# SynchronousRectifier.net
KiCad netlist of a schematic drawn in Altium Designer
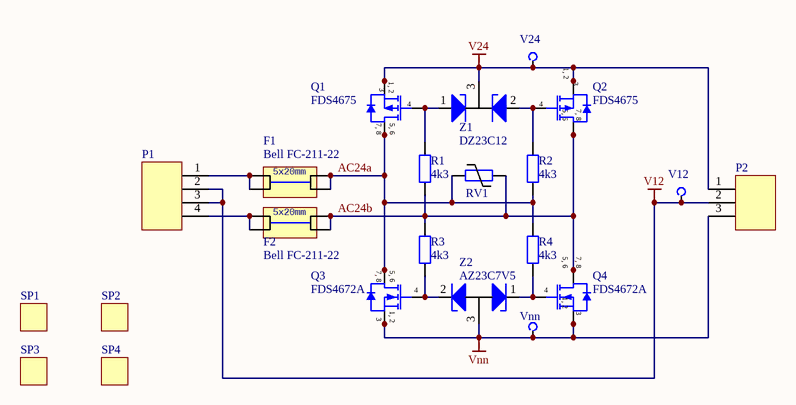
[diagram p0: SynchronousRectifier.SchDoc]

(export (version "E")
  (design (tool "Eeschema 10.0.6"))
  (components
    (comp (ref "F1")
      (value "Bell FC-211-22")
      (footprint "FUSE_CLIP_5x20")
      (description "5x20mm fuse clip PCB Mount")
      (libsource (lib "MySchLib") (part "FUSE_CLIP_5x20"))
    )
    (comp (ref "F2")
      (value "Bell FC-211-22")
      (footprint "FUSE_CLIP_5x20")
      (description "5x20mm fuse clip PCB Mount")
      (libsource (lib "MySchLib") (part "FUSE_CLIP_5x20"))
    )
    (comp (ref "P1")
      (value "Terminal4_5.08mm")
      (footprint "MOLEX-39544-3004")
      (description "MULTICOMP MC24368 TERMINAL BLOCK EUROSTYLE, 4 POSITION, 26-12AWG, 5.08mm")
      (libsource (lib "MyLibrary") (part "Terminal4_5.08mm"))
    )
    (comp (ref "P2")
      (value "Terminal3_5.08mm")
      (footprint "MOLEX-39544-3003")
      (description "MULTICOMP MC24367 TERMINAL BLOCK EUROSTYLE, 3 POSITION, 26-12AWG, 5.08mm")
      (libsource (lib "MyLibrary") (part "Terminal3_5.08mm"))
    )
    (comp (ref "Q1")
      (value "FDS4675")
      (footprint "SO-8_M")
      (fields (field (name "MANUFACTURER") "Fairchild Semiconductor"))
      (libsource (lib "MySchLib") (part "FDS4675"))
    )
    (comp (ref "Q2")
      (value "FDS4675")
      (footprint "SO-8_M")
      (fields (field (name "MANUFACTURER") "Fairchild Semiconductor"))
      (libsource (lib "MySchLib") (part "FDS4675"))
    )
    (comp (ref "Q3")
      (value "FDS4672A")
      (footprint "SO-8_M")
      (description "N-Channel Power MOSFET, 11 A, 40 V. RDS(ON)  = .013 ohm @ VGS = 4.5 V")
      (fields (field (name "MANUFACTURER") "Fairchild Semiconductor"))
      (libsource (lib "MySchLib") (part "FDS4672A"))
    )
    (comp (ref "Q4")
      (value "FDS4672A")
      (footprint "SO-8_M")
      (description "N-Channel Power MOSFET, 11 A, 40 V. RDS(ON)  = .013 ohm @ VGS = 4.5 V")
      (fields (field (name "MANUFACTURER") "Fairchild Semiconductor"))
      (libsource (lib "MySchLib") (part "FDS4672A"))
    )
    (comp (ref "R1")
      (value "4k3")
      (footprint "CR1608-0603_N")
      (description "Resistor SMT 0603")
      (fields
        (field (name "MANUFACTURER") "Generic Components")
        (field (name "PUBLISHER") "Altium Hobart Technology Centre")
      )
      (libsource (lib "MySchLib") (part "Res_CR0603"))
    )
    (comp (ref "R2")
      (value "4k3")
      (footprint "CR1608-0603_N")
      (description "Resistor SMT 0603")
      (fields
        (field (name "MANUFACTURER") "Generic Components")
        (field (name "PUBLISHER") "Altium Hobart Technology Centre")
      )
      (libsource (lib "MySchLib") (part "Res_CR0603"))
    )
    (comp (ref "R3")
      (value "4k3")
      (footprint "CR1608-0603_N")
      (description "Resistor SMT 0603")
      (fields
        (field (name "MANUFACTURER") "Generic Components")
        (field (name "PUBLISHER") "Altium Hobart Technology Centre")
      )
      (libsource (lib "MySchLib") (part "Res_CR0603"))
    )
    (comp (ref "R4")
      (value "4k3")
      (footprint "CR1608-0603_N")
      (description "Resistor SMT 0603")
      (fields
        (field (name "MANUFACTURER") "Generic Components")
        (field (name "PUBLISHER") "Altium Hobart Technology Centre")
      )
      (libsource (lib "MySchLib") (part "Res_CR0603"))
    )
    (comp (ref "RV1")
      (value "V33MLA1206NHAUTO")
      (footprint "VR3216-1206")
      (fields
        (field (name "MANUFACTURER") "Generic Components")
        (field (name "PUBLISHER") "Altium Hobart Technology Centre")
      )
      (libsource (lib "MySchLib") (part "V33MLA1206NHAUTO"))
    )
    (comp (ref "SP1")
      (value "Spacer-3mm-tapped x 10mm")
      (footprint "Spacer-3mm tapped x 10 mm")
      (description "6MM Spacer")
      (libsource (lib "MyLibrary") (part "Spacer-3mm-tapped x 10mm"))
    )
    (comp (ref "SP2")
      (value "Spacer-3mm-tapped x 10mm")
      (footprint "Spacer-3mm tapped x 10 mm")
      (description "6MM Spacer")
      (libsource (lib "MyLibrary") (part "Spacer-3mm-tapped x 10mm"))
    )
    (comp (ref "SP3")
      (value "Spacer-3mm-tapped x 10mm")
      (footprint "Spacer-3mm tapped x 10 mm")
      (description "6MM Spacer")
      (libsource (lib "MyLibrary") (part "Spacer-3mm-tapped x 10mm"))
    )
    (comp (ref "SP4")
      (value "Spacer-3mm-tapped x 10mm")
      (footprint "Spacer-3mm tapped x 10 mm")
      (description "6MM Spacer")
      (libsource (lib "MyLibrary") (part "Spacer-3mm-tapped x 10mm"))
    )
    (comp (ref "V12")
      (value "Power 12V FWR")
      (footprint "PCBPIN - 0.7mm")
      (description "Test Point")
      (libsource (lib "MySchLib") (part "TP"))
    )
    (comp (ref "V24")
      (value "Power 24V FWR")
      (footprint "PCBPIN - 0.7mm")
      (description "Test Point")
      (libsource (lib "MySchLib") (part "TP"))
    )
    (comp (ref "Vnn")
      (value "Power Ground")
      (footprint "PCBPIN - 0.7mm")
      (description "Test Point")
      (libsource (lib "MySchLib") (part "TP"))
    )
    (comp (ref "Z1")
      (value "DZ23C12")
      (footprint "SOT23_M")
      (description "Dual silicon planar Zener diodes")
      (libsource (lib "MySchLib") (part "DZ23Cxx"))
    )
    (comp (ref "Z2")
      (value "AZ23C7V5")
      (footprint "SOT23_M")
      (description "Dual silicon planar Zener diodes")
      (libsource (lib "MySchLib") (part "AZ23Cxx"))
    )
  )
  (nets
    (net (code "1") (name "/AC24a") (class "Default")
      (node (ref "F1") (pin "2") (pinfunction "2_2") (pintype "power_in"))
      (node (ref "F1") (pin "2a") (pinfunction "2a_2a") (pintype "power_in"))
      (node (ref "Q1") (pin "5") (pinfunction "D_5") (pintype "passive"))
      (node (ref "Q1") (pin "6") (pinfunction "D_6") (pintype "passive"))
      (node (ref "Q1") (pin "7") (pinfunction "D_7") (pintype "passive"))
      (node (ref "Q1") (pin "8") (pinfunction "D_8") (pintype "passive"))
      (node (ref "Q3") (pin "5") (pinfunction "D_5") (pintype "passive"))
      (node (ref "Q3") (pin "6") (pinfunction "D_6") (pintype "passive"))
      (node (ref "Q3") (pin "7") (pinfunction "D_7") (pintype "passive"))
      (node (ref "Q3") (pin "8") (pinfunction "D_8") (pintype "passive"))
      (node (ref "R2") (pin "1") (pinfunction "1_1") (pintype "passive"))
      (node (ref "R4") (pin "2") (pinfunction "2_2") (pintype "passive"))
      (node (ref "RV1") (pin "2") (pinfunction "2_2") (pintype "passive"))
    )
    (net (code "2") (name "/AC24b") (class "Default")
      (node (ref "F2") (pin "2") (pinfunction "2_2") (pintype "power_in"))
      (node (ref "F2") (pin "2a") (pinfunction "2a_2a") (pintype "power_in"))
      (node (ref "Q2") (pin "5") (pinfunction "D_5") (pintype "passive"))
      (node (ref "Q2") (pin "6") (pinfunction "D_6") (pintype "passive"))
      (node (ref "Q2") (pin "7") (pinfunction "D_7") (pintype "passive"))
      (node (ref "Q2") (pin "8") (pinfunction "D_8") (pintype "passive"))
      (node (ref "Q4") (pin "5") (pinfunction "D_5") (pintype "passive"))
      (node (ref "Q4") (pin "6") (pinfunction "D_6") (pintype "passive"))
      (node (ref "Q4") (pin "7") (pinfunction "D_7") (pintype "passive"))
      (node (ref "Q4") (pin "8") (pinfunction "D_8") (pintype "passive"))
      (node (ref "R1") (pin "1") (pinfunction "1_1") (pintype "passive"))
      (node (ref "R3") (pin "2") (pinfunction "2_2") (pintype "passive"))
      (node (ref "RV1") (pin "1") (pinfunction "1_1") (pintype "passive"))
    )
    (net (code "3") (name "Net-(F1-Pad1)") (class "Default")
      (node (ref "F1") (pin "1") (pintype "power_in"))
      (node (ref "F1") (pin "1a") (pinfunction "1a_1a") (pintype "power_in"))
      (node (ref "P1") (pin "1") (pinfunction "1_1") (pintype "passive"))
    )
    (net (code "4") (name "Net-(F2-Pad1)") (class "Default")
      (node (ref "F2") (pin "1") (pintype "power_in"))
      (node (ref "F2") (pin "1a") (pinfunction "1a_1a") (pintype "power_in"))
      (node (ref "P1") (pin "4") (pinfunction "4_4") (pintype "passive"))
    )
    (net (code "5") (name "Net-(Q1-G)") (class "Default")
      (node (ref "Q1") (pin "4") (pinfunction "G_4") (pintype "passive"))
      (node (ref "R1") (pin "2") (pinfunction "2_2") (pintype "passive"))
      (node (ref "Z1") (pin "1") (pinfunction "A1_1") (pintype "passive"))
    )
    (net (code "6") (name "Net-(Q2-G)") (class "Default")
      (node (ref "Q2") (pin "4") (pinfunction "G_4") (pintype "passive"))
      (node (ref "R2") (pin "2") (pinfunction "2_2") (pintype "passive"))
      (node (ref "Z1") (pin "2") (pinfunction "A2_2") (pintype "passive"))
    )
    (net (code "7") (name "Net-(Q3-G)") (class "Default")
      (node (ref "Q3") (pin "4") (pinfunction "G_4") (pintype "passive"))
      (node (ref "R3") (pin "1") (pinfunction "1_1") (pintype "passive"))
      (node (ref "Z2") (pin "2") (pinfunction "A2_2") (pintype "passive"))
    )
    (net (code "8") (name "Net-(Q4-G)") (class "Default")
      (node (ref "Q4") (pin "4") (pinfunction "G_4") (pintype "passive"))
      (node (ref "R4") (pin "1") (pinfunction "1_1") (pintype "passive"))
      (node (ref "Z2") (pin "1") (pinfunction "A1_1") (pintype "passive"))
    )
    (net (code "9") (name "V12") (class "Default")
      (node (ref "P1") (pin "2") (pinfunction "2_2") (pintype "passive"))
      (node (ref "P1") (pin "3") (pinfunction "3_3") (pintype "passive"))
      (node (ref "P2") (pin "2") (pinfunction "2_2") (pintype "passive"))
      (node (ref "V12") (pin "1") (pinfunction "TP_1") (pintype "passive"))
    )
    (net (code "10") (name "V24") (class "Default")
      (node (ref "P2") (pin "1") (pinfunction "1_1") (pintype "passive"))
      (node (ref "Q1") (pin "1") (pinfunction "S_1") (pintype "passive"))
      (node (ref "Q1") (pin "2") (pinfunction "S_2") (pintype "passive"))
      (node (ref "Q1") (pin "3") (pinfunction "S_3") (pintype "passive"))
      (node (ref "Q2") (pin "1") (pinfunction "S_1") (pintype "passive"))
      (node (ref "Q2") (pin "2") (pinfunction "S_2") (pintype "passive"))
      (node (ref "Q2") (pin "3") (pinfunction "S_3") (pintype "passive"))
      (node (ref "V24") (pin "1") (pinfunction "TP_1") (pintype "passive"))
      (node (ref "Z1") (pin "3") (pinfunction "K_3") (pintype "passive"))
    )
    (net (code "11") (name "Vnn") (class "Default")
      (node (ref "P2") (pin "3") (pinfunction "3_3") (pintype "passive"))
      (node (ref "Q3") (pin "1") (pinfunction "S_1") (pintype "passive"))
      (node (ref "Q3") (pin "2") (pinfunction "S_2") (pintype "passive"))
      (node (ref "Q3") (pin "3") (pinfunction "S_3") (pintype "passive"))
      (node (ref "Q4") (pin "1") (pinfunction "S_1") (pintype "passive"))
      (node (ref "Q4") (pin "2") (pinfunction "S_2") (pintype "passive"))
      (node (ref "Q4") (pin "3") (pinfunction "S_3") (pintype "passive"))
      (node (ref "Vnn") (pin "1") (pinfunction "TP_1") (pintype "passive"))
      (node (ref "Z2") (pin "3") (pinfunction "K_3") (pintype "passive"))
    )
  )
)
